# Gyro_revb.net
KiCad netlist of a schematic drawn in EAGLE
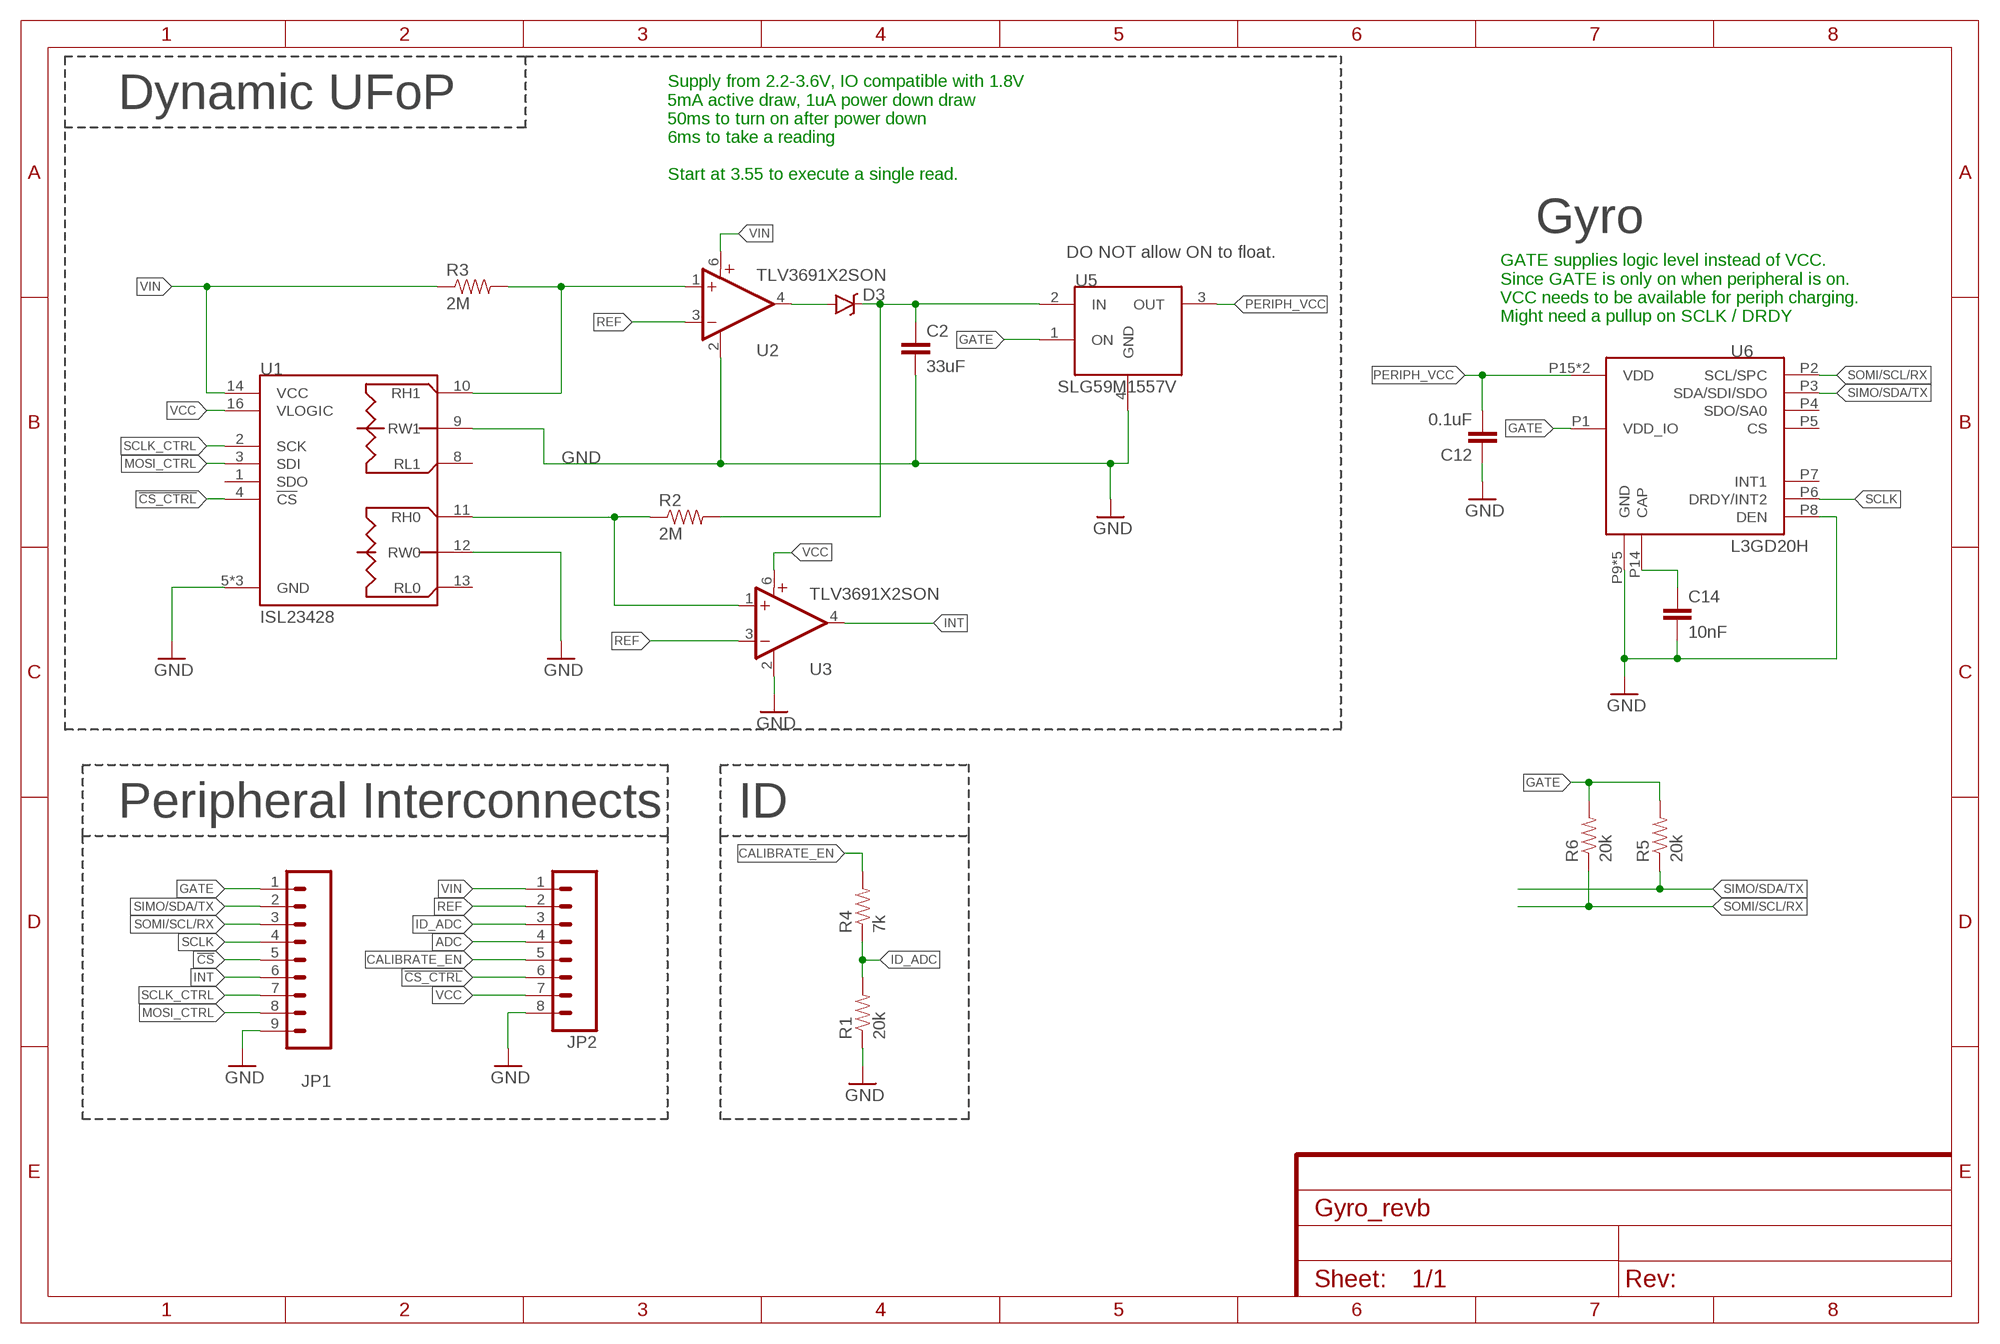
[diagram p0: schematic, sheet 1]

(export (version "E")
  (design (tool "Eeschema 10.0.6"))
  (components
    (comp (ref "C2")
      (value "33uF")
      (footprint "eagle-import:1206")
      (fields (field (name "MPN") "C3216X5R0J336M130AC "))
      (libsource (lib "eagle-import") (part "CAP1206"))
    )
    (comp (ref "C12")
      (value "0.1uF")
      (footprint "eagle-import:0402")
      (fields
        (field (name "MANAFACTURERPARTNUMBER") "  0402YD104KAT2A")
        (field (name "MPN") "0402YD104KAT2A")
      )
      (libsource (lib "eagle-import") (part "C-EU"))
    )
    (comp (ref "C14")
      (value "10nF")
      (footprint "eagle-import:0402")
      (fields (field (name "MPN") "0402YC103KAT2A"))
      (libsource (lib "eagle-import") (part "C-EU"))
    )
    (comp (ref "D3")
      (value "RB751")
      (footprint "eagle-import:SOD-523")
      (fields (field (name "MPN") "BAS40-02V-V-G-08"))
      (libsource (lib "eagle-import") (part "DIODE-SCHOTTKY-RB751"))
    )
    (comp (ref "JP1")
      (value "M091.27MM")
      (footprint "eagle-import:1X09-1.27MM")
      (fields (field (name "MANUFACTURERPARTNUMBER") "GRPB091VWVN-RC "))
      (libsource (lib "eagle-import") (part "M091.27MM"))
    )
    (comp (ref "JP2")
      (value "M081.27MM")
      (footprint "eagle-import:1X08-1.27MM")
      (fields (field (name "MANUFACTURERPARTNUMBER") "GRPB081VWVN-RC "))
      (libsource (lib "eagle-import") (part "M081.27MM"))
    )
    (comp (ref "R1")
      (value "20k")
      (footprint "eagle-import:0402")
      (fields (field (name "MPN") "ERJ-2RKF2002X"))
      (libsource (lib "eagle-import") (part "R-EU"))
    )
    (comp (ref "R2")
      (value "2M")
      (footprint "eagle-import:0402")
      (fields (field (name "MPN") "RC1005F205CS"))
      (libsource (lib "eagle-import") (part "R-EU"))
    )
    (comp (ref "R3")
      (value "2M")
      (footprint "eagle-import:0402")
      (fields (field (name "MPN") "RC1005F205CS"))
      (libsource (lib "eagle-import") (part "R-EU"))
    )
    (comp (ref "R4")
      (value "7k")
      (footprint "eagle-import:0402")
      (fields (field (name "MPN") "RC0402FR-077K15L"))
      (libsource (lib "eagle-import") (part "R-EU"))
    )
    (comp (ref "R5")
      (value "20k")
      (footprint "eagle-import:0402")
      (fields (field (name "MPN") "ERJ-2RKF2002X"))
      (libsource (lib "eagle-import") (part "R-EU"))
    )
    (comp (ref "R6")
      (value "20k")
      (footprint "eagle-import:0402")
      (fields (field (name "MPN") "ERJ-2RKF2002X"))
      (libsource (lib "eagle-import") (part "R-EU"))
    )
    (comp (ref "U1")
      (value "ISL23428")
      (footprint "eagle-import:UTQFN-16")
      (fields (field (name "MPN") "ISL23428TFRUZ-T7A"))
      (libsource (lib "eagle-import") (part "ISL23428"))
    )
    (comp (ref "U2")
      (value "TLV3691X2SON")
      (footprint "eagle-import:X2SON")
      (fields (field (name "MPN") "TLV3691IDPFR"))
      (libsource (lib "eagle-import") (part "TLV3691X2SON"))
    )
    (comp (ref "U3")
      (value "TLV3691X2SON")
      (footprint "eagle-import:X2SON")
      (fields (field (name "MPN") "TLV3691IDPFR"))
      (libsource (lib "eagle-import") (part "TLV3691X2SON"))
    )
    (comp (ref "U5")
      (value "SLG59M1557V")
      (footprint "eagle-import:4STDFN")
      (fields (field (name "MPN") "SLG59M1557V "))
      (libsource (lib "eagle-import") (part "SLG59M1557V"))
    )
    (comp (ref "U6")
      (value "L3GD20H")
      (footprint "eagle-import:LGA16L")
      (fields (field (name "MPN") "L3GD20HTR"))
      (libsource (lib "eagle-import") (part "L3GD20H"))
    )
  )
  (nets
    (net (code "1") (name "/~{CS_CTRL}") (class "Default")
      (node (ref "JP2") (pin "6") (pinfunction "6_6") (pintype "passive"))
      (node (ref "U1") (pin "4") (pinfunction "~{CS}_4") (pintype "bidirectional"))
    )
    (net (code "2") (name "/~{CS}") (class "Default")
      (node (ref "JP1") (pin "5") (pinfunction "5_5") (pintype "passive"))
    )
    (net (code "3") (name "ADC") (class "Default")
      (node (ref "JP2") (pin "4") (pinfunction "4_4") (pintype "passive"))
    )
    (net (code "4") (name "CALIBRATE_EN") (class "Default")
      (node (ref "JP2") (pin "5") (pinfunction "5_5") (pintype "passive"))
      (node (ref "R4") (pin "2") (pinfunction "2_2") (pintype "passive"))
    )
    (net (code "5") (name "GATE") (class "Default")
      (node (ref "JP1") (pin "1") (pinfunction "1_1") (pintype "passive"))
      (node (ref "R5") (pin "2") (pinfunction "2_2") (pintype "passive"))
      (node (ref "R6") (pin "2") (pinfunction "2_2") (pintype "passive"))
      (node (ref "U5") (pin "1") (pinfunction "ON_1") (pintype "bidirectional"))
      (node (ref "U6") (pin "P1") (pinfunction "VDD_IO_P1") (pintype "bidirectional"))
    )
    (net (code "6") (name "GND") (class "Default")
      (node (ref "C12") (pin "1") (pinfunction "1_1") (pintype "passive"))
      (node (ref "C14") (pin "2") (pinfunction "2_2") (pintype "passive"))
      (node (ref "C2") (pin "2") (pinfunction "2_2") (pintype "passive"))
      (node (ref "JP1") (pin "9") (pinfunction "9_9") (pintype "passive"))
      (node (ref "JP2") (pin "8") (pinfunction "8_8") (pintype "passive"))
      (node (ref "R1") (pin "1") (pinfunction "1_1") (pintype "passive"))
      (node (ref "U1") (pin "12") (pinfunction "RW0_12") (pintype "bidirectional"))
      (node (ref "U1") (pin "15") (pinfunction "GND_15") (pintype "bidirectional"))
      (node (ref "U1") (pin "5") (pinfunction "GND_5") (pintype "bidirectional"))
      (node (ref "U1") (pin "6") (pinfunction "GND_6") (pintype "bidirectional"))
      (node (ref "U1") (pin "9") (pinfunction "RW1_9") (pintype "bidirectional"))
      (node (ref "U2") (pin "2") (pinfunction "GND_2") (pintype "power_in"))
      (node (ref "U3") (pin "2") (pinfunction "GND_2") (pintype "power_in"))
      (node (ref "U5") (pin "4") (pinfunction "GND_4") (pintype "bidirectional"))
      (node (ref "U6") (pin "P10") (pinfunction "GND_P10") (pintype "bidirectional"))
      (node (ref "U6") (pin "P11") (pinfunction "GND_P11") (pintype "bidirectional"))
      (node (ref "U6") (pin "P12") (pinfunction "GND_P12") (pintype "bidirectional"))
      (node (ref "U6") (pin "P13") (pinfunction "GND_P13") (pintype "bidirectional"))
      (node (ref "U6") (pin "P8") (pinfunction "DEN_P8") (pintype "bidirectional"))
      (node (ref "U6") (pin "P9") (pinfunction "GND_P9") (pintype "bidirectional"))
    )
    (net (code "7") (name "ID_ADC") (class "Default")
      (node (ref "JP2") (pin "3") (pinfunction "3_3") (pintype "passive"))
      (node (ref "R1") (pin "2") (pinfunction "2_2") (pintype "passive"))
      (node (ref "R4") (pin "1") (pinfunction "1_1") (pintype "passive"))
    )
    (net (code "8") (name "INT") (class "Default")
      (node (ref "JP1") (pin "6") (pinfunction "6_6") (pintype "passive"))
      (node (ref "U3") (pin "4") (pinfunction "OUT_4") (pintype "output"))
    )
    (net (code "9") (name "MOSI_CTRL") (class "Default")
      (node (ref "JP1") (pin "8") (pinfunction "8_8") (pintype "passive"))
      (node (ref "U1") (pin "3") (pinfunction "SDI_3") (pintype "bidirectional"))
    )
    (net (code "10") (name "Net-(U1-RH0)") (class "Default")
      (node (ref "R2") (pin "1") (pinfunction "1_1") (pintype "passive"))
      (node (ref "U1") (pin "11") (pinfunction "RH0_11") (pintype "bidirectional"))
      (node (ref "U3") (pin "1") (pinfunction "+IN_1") (pintype "input"))
    )
    (net (code "11") (name "Net-(U1-RH1)") (class "Default")
      (node (ref "R3") (pin "2") (pinfunction "2_2") (pintype "passive"))
      (node (ref "U1") (pin "10") (pinfunction "RH1_10") (pintype "bidirectional"))
      (node (ref "U2") (pin "1") (pinfunction "+IN_1") (pintype "input"))
    )
    (net (code "12") (name "Net-(U2-OUT)") (class "Default")
      (node (ref "D3") (pin "A") (pinfunction "A_A") (pintype "passive"))
      (node (ref "U2") (pin "4") (pinfunction "OUT_4") (pintype "output"))
    )
    (net (code "13") (name "Net-(U5-IN)") (class "Default")
      (node (ref "C2") (pin "1") (pinfunction "1_1") (pintype "passive"))
      (node (ref "D3") (pin "C") (pinfunction "C_C") (pintype "passive"))
      (node (ref "R2") (pin "2") (pinfunction "2_2") (pintype "passive"))
      (node (ref "U5") (pin "2") (pinfunction "IN_2") (pintype "bidirectional"))
    )
    (net (code "14") (name "Net-(U6-CAP)") (class "Default")
      (node (ref "C14") (pin "1") (pinfunction "1_1") (pintype "passive"))
      (node (ref "U6") (pin "P14") (pinfunction "CAP_P14") (pintype "bidirectional"))
    )
    (net (code "15") (name "PERIPH_VCC") (class "Default")
      (node (ref "C12") (pin "2") (pinfunction "2_2") (pintype "passive"))
      (node (ref "U5") (pin "3") (pinfunction "OUT_3") (pintype "bidirectional"))
      (node (ref "U6") (pin "P15") (pinfunction "VDD_P15") (pintype "bidirectional"))
      (node (ref "U6") (pin "P16") (pinfunction "VDD_P16") (pintype "bidirectional"))
    )
    (net (code "16") (name "REF") (class "Default")
      (node (ref "JP2") (pin "2") (pinfunction "2_2") (pintype "passive"))
      (node (ref "U2") (pin "3") (pinfunction "-IN_3") (pintype "input"))
      (node (ref "U3") (pin "3") (pinfunction "-IN_3") (pintype "input"))
    )
    (net (code "17") (name "SCLK") (class "Default")
      (node (ref "JP1") (pin "4") (pinfunction "4_4") (pintype "passive"))
      (node (ref "U6") (pin "P6") (pinfunction "DRDY/INT2_P6") (pintype "bidirectional"))
    )
    (net (code "18") (name "SCLK_CTRL") (class "Default")
      (node (ref "JP1") (pin "7") (pinfunction "7_7") (pintype "passive"))
      (node (ref "U1") (pin "2") (pinfunction "SCK_2") (pintype "bidirectional"))
    )
    (net (code "19") (name "SIMO{slash}SDA{slash}TX") (class "Default")
      (node (ref "JP1") (pin "2") (pinfunction "2_2") (pintype "passive"))
      (node (ref "R5") (pin "1") (pinfunction "1_1") (pintype "passive"))
      (node (ref "U6") (pin "P3") (pinfunction "SDA/SDI/SDO_P3") (pintype "bidirectional"))
    )
    (net (code "20") (name "SOMI{slash}SCL{slash}RX") (class "Default")
      (node (ref "JP1") (pin "3") (pinfunction "3_3") (pintype "passive"))
      (node (ref "R6") (pin "1") (pinfunction "1_1") (pintype "passive"))
      (node (ref "U6") (pin "P2") (pinfunction "SCL/SPC_P2") (pintype "bidirectional"))
    )
    (net (code "21") (name "VCC") (class "Default")
      (node (ref "JP2") (pin "7") (pinfunction "7_7") (pintype "passive"))
      (node (ref "U1") (pin "16") (pinfunction "VLOGIC_16") (pintype "bidirectional"))
      (node (ref "U3") (pin "6") (pinfunction "V+_6") (pintype "power_in"))
    )
    (net (code "22") (name "VIN") (class "Default")
      (node (ref "JP2") (pin "1") (pinfunction "1_1") (pintype "passive"))
      (node (ref "R3") (pin "1") (pinfunction "1_1") (pintype "passive"))
      (node (ref "U1") (pin "14") (pinfunction "VCC_14") (pintype "bidirectional"))
      (node (ref "U2") (pin "6") (pinfunction "V+_6") (pintype "power_in"))
    )
    (net (code "23") (name "unconnected-(U1-RL0-Pad13)") (class "Default")
      (node (ref "U1") (pin "13") (pinfunction "RL0_13") (pintype "bidirectional"))
    )
    (net (code "24") (name "unconnected-(U1-RL1-Pad8)") (class "Default")
      (node (ref "U1") (pin "8") (pinfunction "RL1_8") (pintype "bidirectional"))
    )
    (net (code "25") (name "unconnected-(U1-SDO-Pad1)") (class "Default")
      (node (ref "U1") (pin "1") (pinfunction "SDO_1") (pintype "bidirectional"))
    )
    (net (code "26") (name "unconnected-(U6-CS-PadP5)") (class "Default")
      (node (ref "U6") (pin "P5") (pinfunction "CS_P5") (pintype "bidirectional"))
    )
    (net (code "27") (name "unconnected-(U6-INT1-PadP7)") (class "Default")
      (node (ref "U6") (pin "P7") (pinfunction "INT1_P7") (pintype "bidirectional"))
    )
    (net (code "28") (name "unconnected-(U6-SDO{slash}SA0-PadP4)") (class "Default")
      (node (ref "U6") (pin "P4") (pinfunction "SDO/SA0_P4") (pintype "bidirectional"))
    )
  )
)
